# potboard.net
KiCad netlist of a schematic drawn in EAGLE
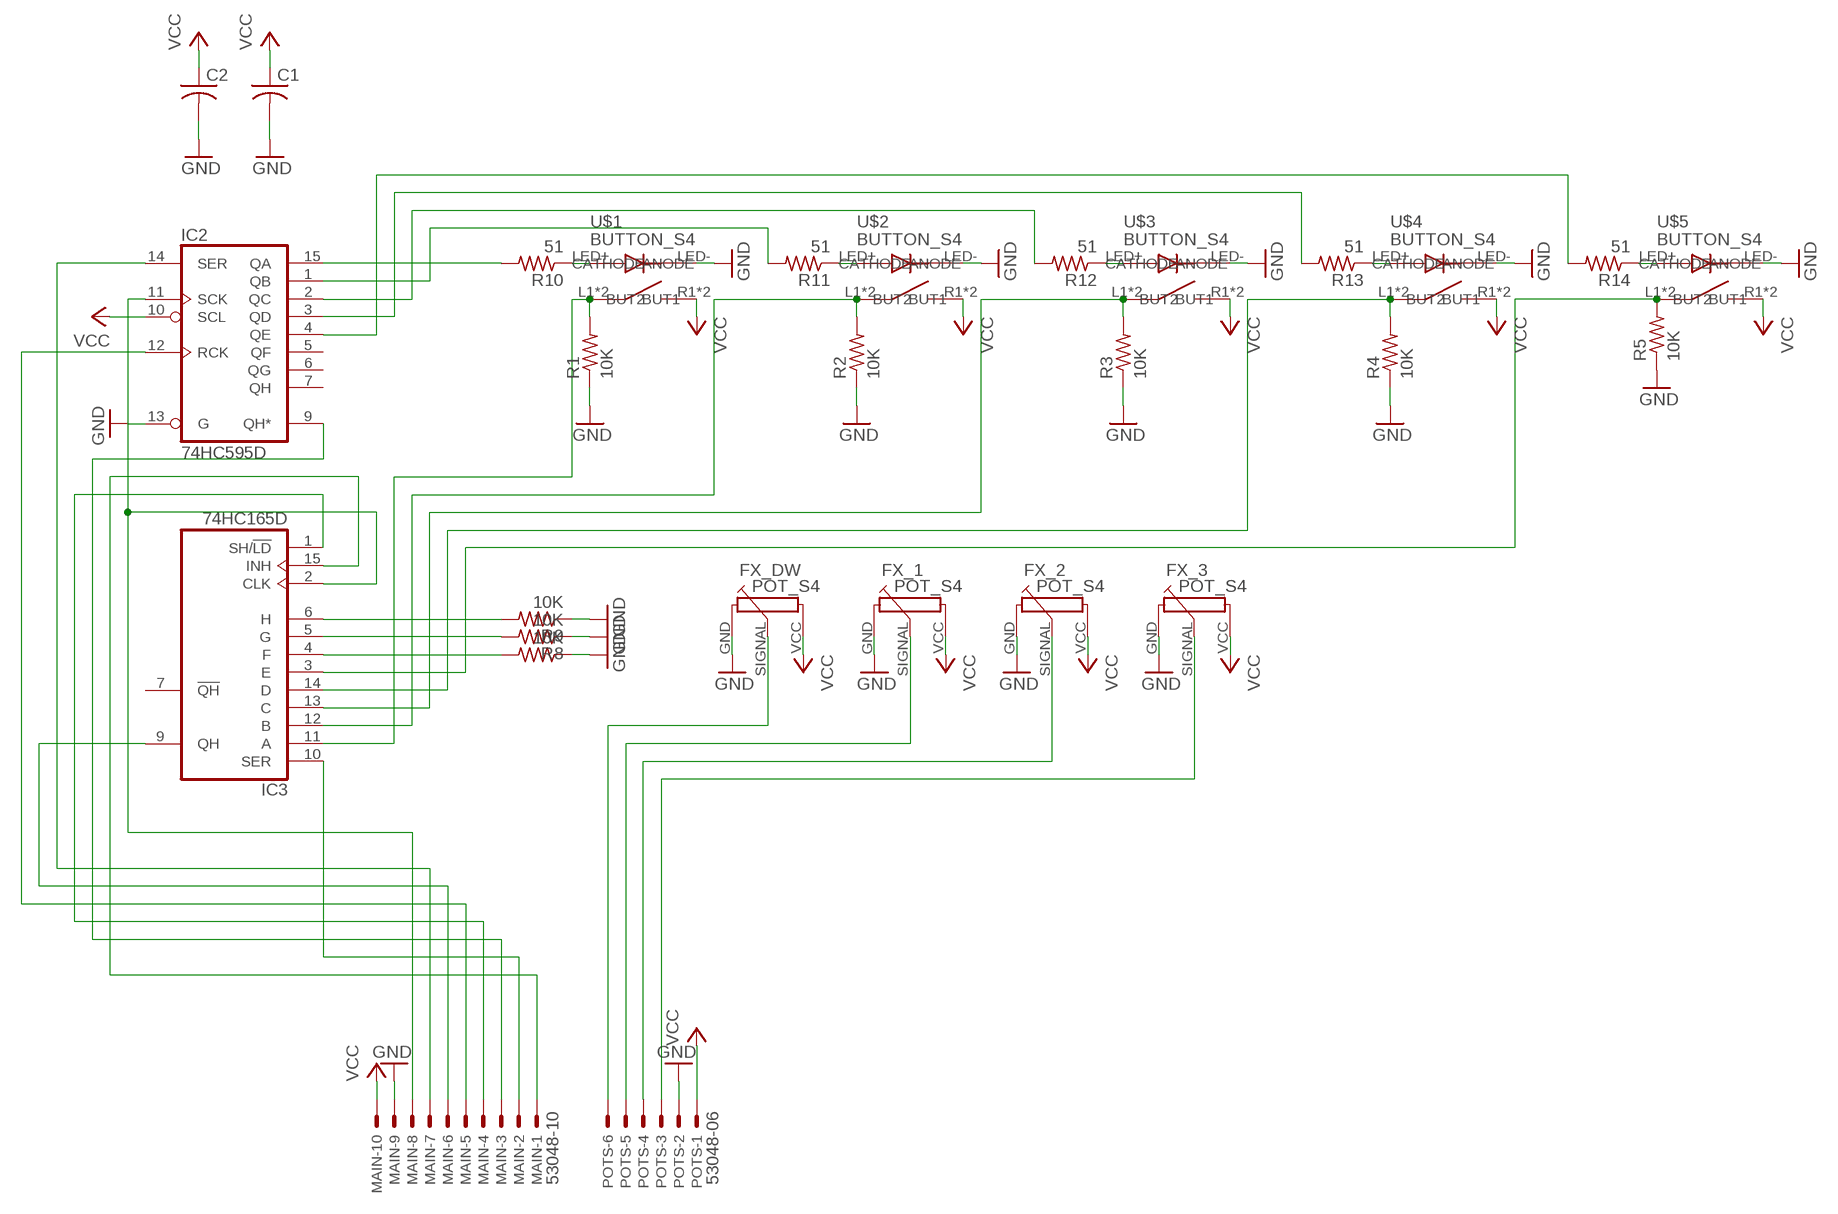
[diagram p0: schematic, sheet 1]

(export (version "E")
  (design (tool "Eeschema 10.0.6"))
  (components
    (comp (ref "C1")
      (value "C-USC1206")
      (footprint "eagle-import:C1206")
      (libsource (lib "eagle-import") (part "C-USC1206"))
    )
    (comp (ref "C2")
      (value "C-USC1206")
      (footprint "eagle-import:C1206")
      (libsource (lib "eagle-import") (part "C-USC1206"))
    )
    (comp (ref "FX_1")
      (value "POT_S4")
      (footprint "eagle-import:POT_S4")
      (libsource (lib "eagle-import") (part "POT_S4"))
    )
    (comp (ref "FX_2")
      (value "POT_S4")
      (footprint "eagle-import:POT_S4")
      (libsource (lib "eagle-import") (part "POT_S4"))
    )
    (comp (ref "FX_3")
      (value "POT_S4")
      (footprint "eagle-import:POT_S4")
      (libsource (lib "eagle-import") (part "POT_S4"))
    )
    (comp (ref "FX_DW")
      (value "POT_S4")
      (footprint "eagle-import:POT_S4")
      (libsource (lib "eagle-import") (part "POT_S4"))
    )
    (comp (ref "IC2")
      (value "74HC595D")
      (footprint "eagle-import:SO16")
      (libsource (lib "eagle-import") (part "74595DHC"))
    )
    (comp (ref "IC3")
      (value "74HC165D")
      (footprint "eagle-import:SO16")
      (libsource (lib "eagle-import") (part "74165DHC"))
    )
    (comp (ref "MAIN")
      (value "53048-10")
      (footprint "eagle-import:53048-10")
      (fields (field (name "MF") "MOLEX") (field (name "MPN") "53048-1010"))
      (libsource (lib "eagle-import") (part "53?-10048"))
    )
    (comp (ref "POTS")
      (value "53048-06")
      (footprint "eagle-import:53048-06")
      (fields (field (name "MF") "WALDOM/MOLEX") (field (name "MPN") "53048-0610"))
      (libsource (lib "eagle-import") (part "53?-06048"))
    )
    (comp (ref "R1")
      (value "10K")
      (footprint "eagle-import:R0805")
      (libsource (lib "eagle-import") (part "R-US_R0805"))
    )
    (comp (ref "R2")
      (value "10K")
      (footprint "eagle-import:R0805")
      (libsource (lib "eagle-import") (part "R-US_R0805"))
    )
    (comp (ref "R3")
      (value "10K")
      (footprint "eagle-import:R0805")
      (libsource (lib "eagle-import") (part "R-US_R0805"))
    )
    (comp (ref "R4")
      (value "10K")
      (footprint "eagle-import:R0805")
      (libsource (lib "eagle-import") (part "R-US_R0805"))
    )
    (comp (ref "R5")
      (value "10K")
      (footprint "eagle-import:R0805")
      (libsource (lib "eagle-import") (part "R-US_R0805"))
    )
    (comp (ref "R6")
      (value "10K")
      (footprint "eagle-import:R0805")
      (libsource (lib "eagle-import") (part "R-US_R0805"))
    )
    (comp (ref "R8")
      (value "10K")
      (footprint "eagle-import:R0805")
      (libsource (lib "eagle-import") (part "R-US_R0805"))
    )
    (comp (ref "R9")
      (value "10K")
      (footprint "eagle-import:R0805")
      (libsource (lib "eagle-import") (part "R-US_R0805"))
    )
    (comp (ref "R10")
      (value "51")
      (footprint "eagle-import:R0805")
      (libsource (lib "eagle-import") (part "R-US_R0805"))
    )
    (comp (ref "R11")
      (value "51")
      (footprint "eagle-import:R0805")
      (libsource (lib "eagle-import") (part "R-US_R0805"))
    )
    (comp (ref "R12")
      (value "51")
      (footprint "eagle-import:R0805")
      (libsource (lib "eagle-import") (part "R-US_R0805"))
    )
    (comp (ref "R13")
      (value "51")
      (footprint "eagle-import:R0805")
      (libsource (lib "eagle-import") (part "R-US_R0805"))
    )
    (comp (ref "R14")
      (value "51")
      (footprint "eagle-import:R0805")
      (libsource (lib "eagle-import") (part "R-US_R0805"))
    )
    (comp (ref "U$1")
      (value "BUTTON_S4")
      (footprint "eagle-import:BUTTON_S4")
      (libsource (lib "eagle-import") (part "BUTTON_S4"))
    )
    (comp (ref "U$2")
      (value "BUTTON_S4")
      (footprint "eagle-import:BUTTON_S4")
      (libsource (lib "eagle-import") (part "BUTTON_S4"))
    )
    (comp (ref "U$3")
      (value "BUTTON_S4")
      (footprint "eagle-import:BUTTON_S4")
      (libsource (lib "eagle-import") (part "BUTTON_S4"))
    )
    (comp (ref "U$4")
      (value "BUTTON_S4")
      (footprint "eagle-import:BUTTON_S4")
      (libsource (lib "eagle-import") (part "BUTTON_S4"))
    )
    (comp (ref "U$5")
      (value "BUTTON_S4")
      (footprint "eagle-import:BUTTON_S4")
      (libsource (lib "eagle-import") (part "BUTTON_S4"))
    )
  )
  (nets
    (net (code "1") (name "GND") (class "Default")
      (node (ref "C1") (pin "2") (pinfunction "2_2") (pintype "passive"))
      (node (ref "C2") (pin "2") (pinfunction "2_2") (pintype "passive"))
      (node (ref "FX_1") (pin "GND") (pinfunction "1A_GND") (pintype "passive"))
      (node (ref "FX_2") (pin "GND") (pinfunction "1A_GND") (pintype "passive"))
      (node (ref "FX_3") (pin "GND") (pinfunction "1A_GND") (pintype "passive"))
      (node (ref "FX_DW") (pin "GND") (pinfunction "1A_GND") (pintype "passive"))
      (node (ref "IC2") (pin "13") (pinfunction "G_13") (pintype "input"))
      (node (ref "MAIN") (pin "9") (pinfunction "S_9") (pintype "passive"))
      (node (ref "POTS") (pin "2") (pinfunction "S_2") (pintype "passive"))
      (node (ref "R1") (pin "1") (pinfunction "1_1") (pintype "passive"))
      (node (ref "R2") (pin "1") (pinfunction "1_1") (pintype "passive"))
      (node (ref "R3") (pin "1") (pinfunction "1_1") (pintype "passive"))
      (node (ref "R4") (pin "1") (pinfunction "1_1") (pintype "passive"))
      (node (ref "R5") (pin "1") (pinfunction "1_1") (pintype "passive"))
      (node (ref "R6") (pin "1") (pinfunction "1_1") (pintype "passive"))
      (node (ref "R8") (pin "1") (pinfunction "1_1") (pintype "passive"))
      (node (ref "R9") (pin "1") (pinfunction "1_1") (pintype "passive"))
      (node (ref "U$1") (pin "LED-") (pinfunction "CATHODE_LED-") (pintype "bidirectional"))
      (node (ref "U$2") (pin "LED-") (pinfunction "CATHODE_LED-") (pintype "bidirectional"))
      (node (ref "U$3") (pin "LED-") (pinfunction "CATHODE_LED-") (pintype "bidirectional"))
      (node (ref "U$4") (pin "LED-") (pinfunction "CATHODE_LED-") (pintype "bidirectional"))
      (node (ref "U$5") (pin "LED-") (pinfunction "CATHODE_LED-") (pintype "bidirectional"))
    )
    (net (code "2") (name "Net-(FX_1-1S)") (class "Default")
      (node (ref "FX_1") (pin "SIGNAL") (pinfunction "1S_SIGNAL") (pintype "passive"))
      (node (ref "POTS") (pin "5") (pinfunction "S_5") (pintype "passive"))
    )
    (net (code "3") (name "Net-(FX_2-1S)") (class "Default")
      (node (ref "FX_2") (pin "SIGNAL") (pinfunction "1S_SIGNAL") (pintype "passive"))
      (node (ref "POTS") (pin "4") (pinfunction "S_4") (pintype "passive"))
    )
    (net (code "4") (name "Net-(FX_3-1S)") (class "Default")
      (node (ref "FX_3") (pin "SIGNAL") (pinfunction "1S_SIGNAL") (pintype "passive"))
      (node (ref "POTS") (pin "3") (pinfunction "S_3") (pintype "passive"))
    )
    (net (code "5") (name "Net-(FX_DW-1S)") (class "Default")
      (node (ref "FX_DW") (pin "SIGNAL") (pinfunction "1S_SIGNAL") (pintype "passive"))
      (node (ref "POTS") (pin "6") (pinfunction "S_6") (pintype "passive"))
    )
    (net (code "6") (name "Net-(IC2A-QA)") (class "Default")
      (node (ref "IC2") (pin "15") (pinfunction "QA_15") (pintype "tri_state"))
      (node (ref "R10") (pin "2") (pinfunction "2_2") (pintype "passive"))
    )
    (net (code "7") (name "Net-(IC2A-QB)") (class "Default")
      (node (ref "IC2") (pin "1") (pinfunction "QB_1") (pintype "tri_state"))
      (node (ref "R11") (pin "2") (pinfunction "2_2") (pintype "passive"))
    )
    (net (code "8") (name "Net-(IC2A-QC)") (class "Default")
      (node (ref "IC2") (pin "2") (pinfunction "QC_2") (pintype "tri_state"))
      (node (ref "R12") (pin "2") (pinfunction "2_2") (pintype "passive"))
    )
    (net (code "9") (name "Net-(IC2A-QD)") (class "Default")
      (node (ref "IC2") (pin "3") (pinfunction "QD_3") (pintype "tri_state"))
      (node (ref "R13") (pin "2") (pinfunction "2_2") (pintype "passive"))
    )
    (net (code "10") (name "Net-(IC2A-QE)") (class "Default")
      (node (ref "IC2") (pin "4") (pinfunction "QE_4") (pintype "tri_state"))
      (node (ref "R14") (pin "2") (pinfunction "2_2") (pintype "passive"))
    )
    (net (code "11") (name "Net-(IC2A-QH*)") (class "Default")
      (node (ref "IC2") (pin "9") (pinfunction "QH*_9") (pintype "tri_state"))
      (node (ref "MAIN") (pin "3") (pinfunction "S_3") (pintype "passive"))
    )
    (net (code "12") (name "Net-(IC2A-RCK)") (class "Default")
      (node (ref "IC2") (pin "12") (pinfunction "RCK_12") (pintype "input"))
      (node (ref "MAIN") (pin "5") (pinfunction "S_5") (pintype "passive"))
    )
    (net (code "13") (name "Net-(IC2A-SCK)") (class "Default")
      (node (ref "IC2") (pin "11") (pinfunction "SCK_11") (pintype "input"))
      (node (ref "IC3") (pin "2") (pinfunction "CLK_2") (pintype "input"))
      (node (ref "MAIN") (pin "8") (pinfunction "S_8") (pintype "passive"))
    )
    (net (code "14") (name "Net-(IC2A-SER)") (class "Default")
      (node (ref "IC2") (pin "14") (pinfunction "SER_14") (pintype "input"))
      (node (ref "MAIN") (pin "7") (pinfunction "S_7") (pintype "passive"))
    )
    (net (code "15") (name "Net-(IC3A-A)") (class "Default")
      (node (ref "IC3") (pin "11") (pinfunction "A_11") (pintype "input"))
      (node (ref "R1") (pin "2") (pinfunction "2_2") (pintype "passive"))
      (node (ref "U$1") (pin "L1") (pinfunction "BUT1_L1") (pintype "bidirectional"))
      (node (ref "U$1") (pin "L2") (pinfunction "BUT1_L2") (pintype "bidirectional"))
    )
    (net (code "16") (name "Net-(IC3A-B)") (class "Default")
      (node (ref "IC3") (pin "12") (pinfunction "B_12") (pintype "input"))
      (node (ref "R2") (pin "2") (pinfunction "2_2") (pintype "passive"))
      (node (ref "U$2") (pin "L1") (pinfunction "BUT1_L1") (pintype "bidirectional"))
      (node (ref "U$2") (pin "L2") (pinfunction "BUT1_L2") (pintype "bidirectional"))
    )
    (net (code "17") (name "Net-(IC3A-C)") (class "Default")
      (node (ref "IC3") (pin "13") (pinfunction "C_13") (pintype "input"))
      (node (ref "R3") (pin "2") (pinfunction "2_2") (pintype "passive"))
      (node (ref "U$3") (pin "L1") (pinfunction "BUT1_L1") (pintype "bidirectional"))
      (node (ref "U$3") (pin "L2") (pinfunction "BUT1_L2") (pintype "bidirectional"))
    )
    (net (code "18") (name "Net-(IC3A-D)") (class "Default")
      (node (ref "IC3") (pin "14") (pinfunction "D_14") (pintype "input"))
      (node (ref "R4") (pin "2") (pinfunction "2_2") (pintype "passive"))
      (node (ref "U$4") (pin "L1") (pinfunction "BUT1_L1") (pintype "bidirectional"))
      (node (ref "U$4") (pin "L2") (pinfunction "BUT1_L2") (pintype "bidirectional"))
    )
    (net (code "19") (name "Net-(IC3A-E)") (class "Default")
      (node (ref "IC3") (pin "3") (pinfunction "E_3") (pintype "input"))
      (node (ref "R5") (pin "2") (pinfunction "2_2") (pintype "passive"))
      (node (ref "U$5") (pin "L1") (pinfunction "BUT1_L1") (pintype "bidirectional"))
      (node (ref "U$5") (pin "L2") (pinfunction "BUT1_L2") (pintype "bidirectional"))
    )
    (net (code "20") (name "Net-(IC3A-F)") (class "Default")
      (node (ref "IC3") (pin "4") (pinfunction "F_4") (pintype "input"))
      (node (ref "R6") (pin "2") (pinfunction "2_2") (pintype "passive"))
    )
    (net (code "21") (name "Net-(IC3A-G)") (class "Default")
      (node (ref "IC3") (pin "5") (pinfunction "G_5") (pintype "input"))
      (node (ref "R8") (pin "2") (pinfunction "2_2") (pintype "passive"))
    )
    (net (code "22") (name "Net-(IC3A-H)") (class "Default")
      (node (ref "IC3") (pin "6") (pinfunction "H_6") (pintype "input"))
      (node (ref "R9") (pin "2") (pinfunction "2_2") (pintype "passive"))
    )
    (net (code "23") (name "Net-(IC3A-INH)") (class "Default")
      (node (ref "IC3") (pin "15") (pinfunction "INH_15") (pintype "input"))
      (node (ref "MAIN") (pin "1") (pinfunction "S_1") (pintype "passive"))
    )
    (net (code "24") (name "Net-(IC3A-QH)") (class "Default")
      (node (ref "IC3") (pin "9") (pinfunction "QH_9") (pintype "output"))
      (node (ref "MAIN") (pin "6") (pinfunction "S_6") (pintype "passive"))
    )
    (net (code "25") (name "Net-(IC3A-SER)") (class "Default")
      (node (ref "IC3") (pin "10") (pinfunction "SER_10") (pintype "input"))
      (node (ref "MAIN") (pin "2") (pinfunction "S_2") (pintype "passive"))
    )
    (net (code "26") (name "Net-(IC3A-SH{slash}~{LD})") (class "Default")
      (node (ref "IC3") (pin "1") (pinfunction "SH/~{LD}_1") (pintype "input"))
      (node (ref "MAIN") (pin "4") (pinfunction "S_4") (pintype "passive"))
    )
    (net (code "27") (name "Net-(U$1-ANODE)") (class "Default")
      (node (ref "R10") (pin "1") (pinfunction "1_1") (pintype "passive"))
      (node (ref "U$1") (pin "LED+") (pinfunction "ANODE_LED+") (pintype "bidirectional"))
    )
    (net (code "28") (name "Net-(U$2-ANODE)") (class "Default")
      (node (ref "R11") (pin "1") (pinfunction "1_1") (pintype "passive"))
      (node (ref "U$2") (pin "LED+") (pinfunction "ANODE_LED+") (pintype "bidirectional"))
    )
    (net (code "29") (name "Net-(U$3-ANODE)") (class "Default")
      (node (ref "R12") (pin "1") (pinfunction "1_1") (pintype "passive"))
      (node (ref "U$3") (pin "LED+") (pinfunction "ANODE_LED+") (pintype "bidirectional"))
    )
    (net (code "30") (name "Net-(U$4-ANODE)") (class "Default")
      (node (ref "R13") (pin "1") (pinfunction "1_1") (pintype "passive"))
      (node (ref "U$4") (pin "LED+") (pinfunction "ANODE_LED+") (pintype "bidirectional"))
    )
    (net (code "31") (name "Net-(U$5-ANODE)") (class "Default")
      (node (ref "R14") (pin "1") (pinfunction "1_1") (pintype "passive"))
      (node (ref "U$5") (pin "LED+") (pinfunction "ANODE_LED+") (pintype "bidirectional"))
    )
    (net (code "32") (name "VCC") (class "Default")
      (node (ref "C1") (pin "1") (pinfunction "1_1") (pintype "passive"))
      (node (ref "C2") (pin "1") (pinfunction "1_1") (pintype "passive"))
      (node (ref "FX_1") (pin "VCC") (pinfunction "1E_VCC") (pintype "passive"))
      (node (ref "FX_2") (pin "VCC") (pinfunction "1E_VCC") (pintype "passive"))
      (node (ref "FX_3") (pin "VCC") (pinfunction "1E_VCC") (pintype "passive"))
      (node (ref "FX_DW") (pin "VCC") (pinfunction "1E_VCC") (pintype "passive"))
      (node (ref "IC2") (pin "10") (pinfunction "SCL_10") (pintype "input"))
      (node (ref "MAIN") (pin "10") (pinfunction "S_10") (pintype "passive"))
      (node (ref "POTS") (pin "1") (pinfunction "S_1") (pintype "passive"))
      (node (ref "U$1") (pin "R1") (pinfunction "BUT2_R1") (pintype "bidirectional"))
      (node (ref "U$1") (pin "R2") (pinfunction "BUT2_R2") (pintype "bidirectional"))
      (node (ref "U$2") (pin "R1") (pinfunction "BUT2_R1") (pintype "bidirectional"))
      (node (ref "U$2") (pin "R2") (pinfunction "BUT2_R2") (pintype "bidirectional"))
      (node (ref "U$3") (pin "R1") (pinfunction "BUT2_R1") (pintype "bidirectional"))
      (node (ref "U$3") (pin "R2") (pinfunction "BUT2_R2") (pintype "bidirectional"))
      (node (ref "U$4") (pin "R1") (pinfunction "BUT2_R1") (pintype "bidirectional"))
      (node (ref "U$4") (pin "R2") (pinfunction "BUT2_R2") (pintype "bidirectional"))
      (node (ref "U$5") (pin "R1") (pinfunction "BUT2_R1") (pintype "bidirectional"))
      (node (ref "U$5") (pin "R2") (pinfunction "BUT2_R2") (pintype "bidirectional"))
    )
    (net (code "33") (name "unconnected-(IC2A-QF-Pad5)") (class "Default")
      (node (ref "IC2") (pin "5") (pinfunction "QF_5") (pintype "tri_state"))
    )
    (net (code "34") (name "unconnected-(IC2A-QG-Pad6)") (class "Default")
      (node (ref "IC2") (pin "6") (pinfunction "QG_6") (pintype "tri_state"))
    )
    (net (code "35") (name "unconnected-(IC2A-QH-Pad7)") (class "Default")
      (node (ref "IC2") (pin "7") (pinfunction "QH_7") (pintype "tri_state"))
    )
    (net (code "36") (name "unconnected-(IC3A-~{QH}-Pad7)") (class "Default")
      (node (ref "IC3") (pin "7") (pinfunction "~{QH}_7") (pintype "output"))
    )
  )
)
